# avr-fusebit-doctor-adapter-tqfp32.net
KiCad netlist of a schematic drawn in EAGLE
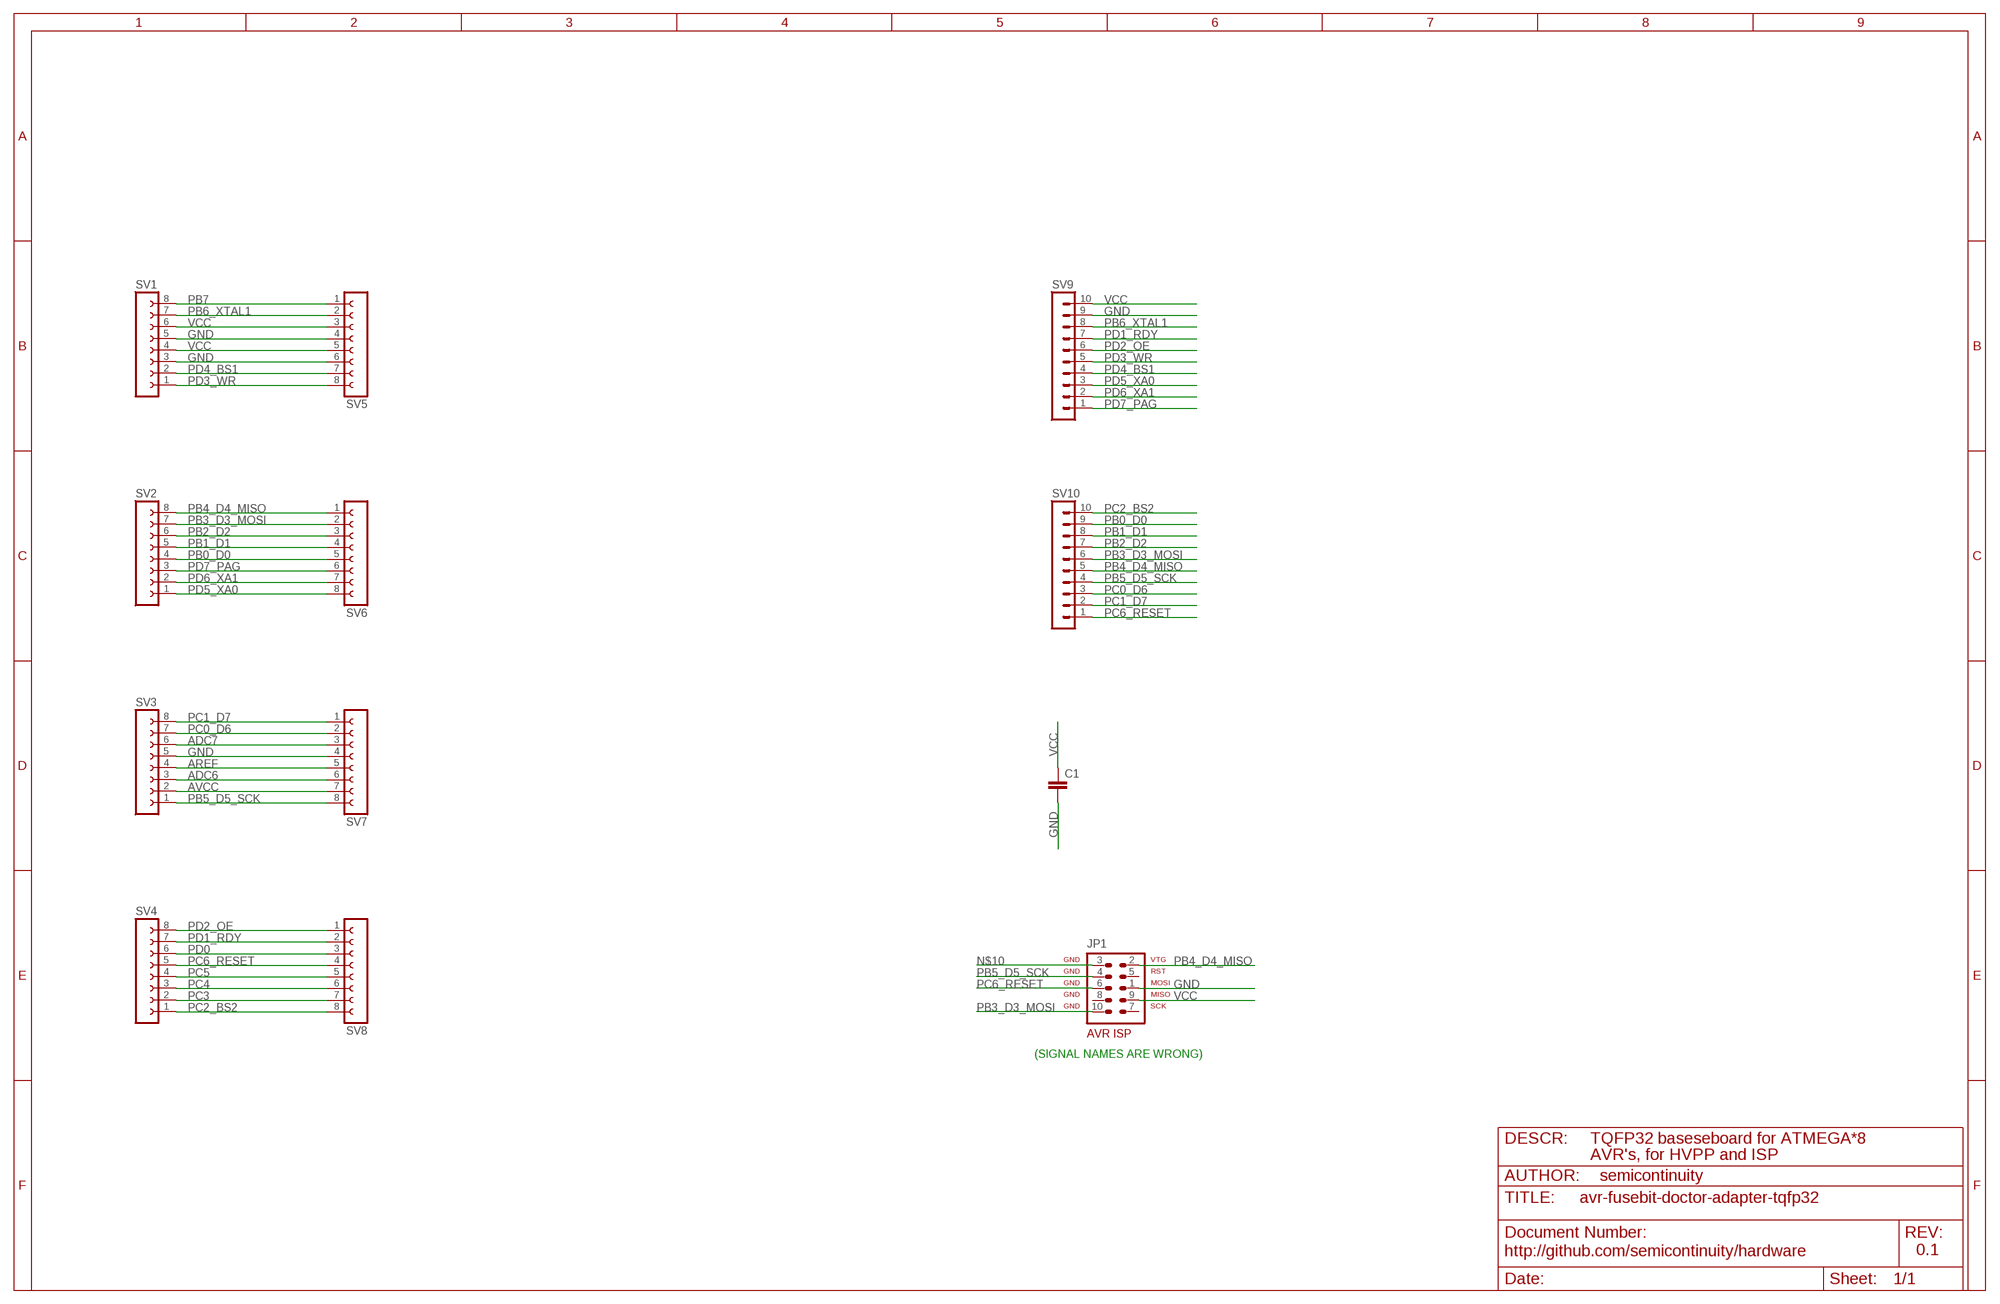
[diagram p0: schematic, sheet 1]

(export (version "E")
  (design (tool "Eeschema 10.0.6"))
  (components
    (comp (ref "C1")
      (value "C-EUC0805")
      (footprint "eagle-import:C0805")
      (libsource (lib "eagle-import") (part "C-EUC0805"))
    )
    (comp (ref "JP1")
      (value "AVR-ISP-10")
      (footprint "eagle-import:AVR-ISP-10")
      (libsource (lib "eagle-import") (part "AVR-ISP-10"))
    )
    (comp (ref "SV1")
      (value "FE08-1")
      (footprint "eagle-import:FE08")
      (libsource (lib "eagle-import") (part "FE08-1"))
    )
    (comp (ref "SV2")
      (value "FE08-1")
      (footprint "eagle-import:FE08")
      (libsource (lib "eagle-import") (part "FE08-1"))
    )
    (comp (ref "SV3")
      (value "FE08-1")
      (footprint "eagle-import:FE08")
      (libsource (lib "eagle-import") (part "FE08-1"))
    )
    (comp (ref "SV4")
      (value "FE08-1")
      (footprint "eagle-import:FE08")
      (libsource (lib "eagle-import") (part "FE08-1"))
    )
    (comp (ref "SV5")
      (value "FE08-1")
      (footprint "eagle-import:FE08")
      (libsource (lib "eagle-import") (part "FE08-1"))
    )
    (comp (ref "SV6")
      (value "FE08-1")
      (footprint "eagle-import:FE08")
      (libsource (lib "eagle-import") (part "FE08-1"))
    )
    (comp (ref "SV7")
      (value "FE08-1")
      (footprint "eagle-import:FE08")
      (libsource (lib "eagle-import") (part "FE08-1"))
    )
    (comp (ref "SV8")
      (value "FE08-1")
      (footprint "eagle-import:FE08")
      (libsource (lib "eagle-import") (part "FE08-1"))
    )
    (comp (ref "SV9")
      (value "MA10-1")
      (footprint "eagle-import:MA10-1")
      (libsource (lib "eagle-import") (part "MA10-1"))
    )
    (comp (ref "SV10")
      (value "MA10-1")
      (footprint "eagle-import:MA10-1")
      (libsource (lib "eagle-import") (part "MA10-1"))
    )
  )
  (nets
    (net (code "1") (name "/ADC6") (class "Default")
      (node (ref "SV3") (pin "3") (pinfunction "3_3") (pintype "passive"))
      (node (ref "SV7") (pin "6") (pinfunction "6_6") (pintype "passive"))
    )
    (net (code "2") (name "/ADC7") (class "Default")
      (node (ref "SV3") (pin "6") (pinfunction "6_6") (pintype "passive"))
      (node (ref "SV7") (pin "3") (pinfunction "3_3") (pintype "passive"))
    )
    (net (code "3") (name "/AREF") (class "Default")
      (node (ref "SV3") (pin "4") (pinfunction "4_4") (pintype "passive"))
      (node (ref "SV7") (pin "5") (pinfunction "5_5") (pintype "passive"))
    )
    (net (code "4") (name "/AVCC") (class "Default")
      (node (ref "SV3") (pin "2") (pinfunction "2_2") (pintype "passive"))
      (node (ref "SV7") (pin "7") (pinfunction "7_7") (pintype "passive"))
    )
    (net (code "5") (name "/GND") (class "Default")
      (node (ref "C1") (pin "2") (pinfunction "2_2") (pintype "passive"))
      (node (ref "JP1") (pin "1") (pinfunction "1_1") (pintype "passive"))
      (node (ref "SV1") (pin "3") (pinfunction "3_3") (pintype "passive"))
      (node (ref "SV1") (pin "5") (pinfunction "5_5") (pintype "passive"))
      (node (ref "SV3") (pin "5") (pinfunction "5_5") (pintype "passive"))
      (node (ref "SV5") (pin "4") (pinfunction "4_4") (pintype "passive"))
      (node (ref "SV5") (pin "6") (pinfunction "6_6") (pintype "passive"))
      (node (ref "SV7") (pin "4") (pinfunction "4_4") (pintype "passive"))
      (node (ref "SV9") (pin "9") (pinfunction "9_9") (pintype "passive"))
    )
    (net (code "6") (name "/N$10") (class "Default")
      (node (ref "JP1") (pin "3") (pinfunction "3_3") (pintype "passive"))
    )
    (net (code "7") (name "/PB0_D0") (class "Default")
      (node (ref "SV10") (pin "9") (pinfunction "9_9") (pintype "passive"))
      (node (ref "SV2") (pin "4") (pinfunction "4_4") (pintype "passive"))
      (node (ref "SV6") (pin "5") (pinfunction "5_5") (pintype "passive"))
    )
    (net (code "8") (name "/PB1_D1") (class "Default")
      (node (ref "SV10") (pin "8") (pinfunction "8_8") (pintype "passive"))
      (node (ref "SV2") (pin "5") (pinfunction "5_5") (pintype "passive"))
      (node (ref "SV6") (pin "4") (pinfunction "4_4") (pintype "passive"))
    )
    (net (code "9") (name "/PB2_D2") (class "Default")
      (node (ref "SV10") (pin "7") (pinfunction "7_7") (pintype "passive"))
      (node (ref "SV2") (pin "6") (pinfunction "6_6") (pintype "passive"))
      (node (ref "SV6") (pin "3") (pinfunction "3_3") (pintype "passive"))
    )
    (net (code "10") (name "/PB3_D3_MOSI") (class "Default")
      (node (ref "JP1") (pin "10") (pinfunction "10_10") (pintype "passive"))
      (node (ref "SV10") (pin "6") (pinfunction "6_6") (pintype "passive"))
      (node (ref "SV2") (pin "7") (pinfunction "7_7") (pintype "passive"))
      (node (ref "SV6") (pin "2") (pinfunction "2_2") (pintype "passive"))
    )
    (net (code "11") (name "/PB4_D4_MISO") (class "Default")
      (node (ref "JP1") (pin "2") (pinfunction "2_2") (pintype "passive"))
      (node (ref "SV10") (pin "5") (pinfunction "5_5") (pintype "passive"))
      (node (ref "SV2") (pin "8") (pinfunction "8_8") (pintype "passive"))
      (node (ref "SV6") (pin "1") (pinfunction "1_1") (pintype "passive"))
    )
    (net (code "12") (name "/PB5_D5_SCK") (class "Default")
      (node (ref "JP1") (pin "4") (pinfunction "4_4") (pintype "passive"))
      (node (ref "SV10") (pin "4") (pinfunction "4_4") (pintype "passive"))
      (node (ref "SV3") (pin "1") (pinfunction "1_1") (pintype "passive"))
      (node (ref "SV7") (pin "8") (pinfunction "8_8") (pintype "passive"))
    )
    (net (code "13") (name "/PB6_XTAL1") (class "Default")
      (node (ref "SV1") (pin "7") (pinfunction "7_7") (pintype "passive"))
      (node (ref "SV5") (pin "2") (pinfunction "2_2") (pintype "passive"))
      (node (ref "SV9") (pin "8") (pinfunction "8_8") (pintype "passive"))
    )
    (net (code "14") (name "/PB7") (class "Default")
      (node (ref "SV1") (pin "8") (pinfunction "8_8") (pintype "passive"))
      (node (ref "SV5") (pin "1") (pinfunction "1_1") (pintype "passive"))
    )
    (net (code "15") (name "/PC0_D6") (class "Default")
      (node (ref "SV10") (pin "3") (pinfunction "3_3") (pintype "passive"))
      (node (ref "SV3") (pin "7") (pinfunction "7_7") (pintype "passive"))
      (node (ref "SV7") (pin "2") (pinfunction "2_2") (pintype "passive"))
    )
    (net (code "16") (name "/PC1_D7") (class "Default")
      (node (ref "SV10") (pin "2") (pinfunction "2_2") (pintype "passive"))
      (node (ref "SV3") (pin "8") (pinfunction "8_8") (pintype "passive"))
      (node (ref "SV7") (pin "1") (pinfunction "1_1") (pintype "passive"))
    )
    (net (code "17") (name "/PC2_BS2") (class "Default")
      (node (ref "SV10") (pin "10") (pinfunction "10_10") (pintype "passive"))
      (node (ref "SV4") (pin "1") (pinfunction "1_1") (pintype "passive"))
      (node (ref "SV8") (pin "8") (pinfunction "8_8") (pintype "passive"))
    )
    (net (code "18") (name "/PC3") (class "Default")
      (node (ref "SV4") (pin "2") (pinfunction "2_2") (pintype "passive"))
      (node (ref "SV8") (pin "7") (pinfunction "7_7") (pintype "passive"))
    )
    (net (code "19") (name "/PC4") (class "Default")
      (node (ref "SV4") (pin "3") (pinfunction "3_3") (pintype "passive"))
      (node (ref "SV8") (pin "6") (pinfunction "6_6") (pintype "passive"))
    )
    (net (code "20") (name "/PC5") (class "Default")
      (node (ref "SV4") (pin "4") (pinfunction "4_4") (pintype "passive"))
      (node (ref "SV8") (pin "5") (pinfunction "5_5") (pintype "passive"))
    )
    (net (code "21") (name "/PC6_RESET") (class "Default")
      (node (ref "JP1") (pin "6") (pinfunction "6_6") (pintype "passive"))
      (node (ref "SV10") (pin "1") (pinfunction "1_1") (pintype "passive"))
      (node (ref "SV4") (pin "5") (pinfunction "5_5") (pintype "passive"))
      (node (ref "SV8") (pin "4") (pinfunction "4_4") (pintype "passive"))
    )
    (net (code "22") (name "/PD0") (class "Default")
      (node (ref "SV4") (pin "6") (pinfunction "6_6") (pintype "passive"))
      (node (ref "SV8") (pin "3") (pinfunction "3_3") (pintype "passive"))
    )
    (net (code "23") (name "/PD1_RDY") (class "Default")
      (node (ref "SV4") (pin "7") (pinfunction "7_7") (pintype "passive"))
      (node (ref "SV8") (pin "2") (pinfunction "2_2") (pintype "passive"))
      (node (ref "SV9") (pin "7") (pinfunction "7_7") (pintype "passive"))
    )
    (net (code "24") (name "/PD2_OE") (class "Default")
      (node (ref "SV4") (pin "8") (pinfunction "8_8") (pintype "passive"))
      (node (ref "SV8") (pin "1") (pinfunction "1_1") (pintype "passive"))
      (node (ref "SV9") (pin "6") (pinfunction "6_6") (pintype "passive"))
    )
    (net (code "25") (name "/PD3_WR") (class "Default")
      (node (ref "SV1") (pin "1") (pinfunction "1_1") (pintype "passive"))
      (node (ref "SV5") (pin "8") (pinfunction "8_8") (pintype "passive"))
      (node (ref "SV9") (pin "5") (pinfunction "5_5") (pintype "passive"))
    )
    (net (code "26") (name "/PD4_BS1") (class "Default")
      (node (ref "SV1") (pin "2") (pinfunction "2_2") (pintype "passive"))
      (node (ref "SV5") (pin "7") (pinfunction "7_7") (pintype "passive"))
      (node (ref "SV9") (pin "4") (pinfunction "4_4") (pintype "passive"))
    )
    (net (code "27") (name "/PD5_XA0") (class "Default")
      (node (ref "SV2") (pin "1") (pinfunction "1_1") (pintype "passive"))
      (node (ref "SV6") (pin "8") (pinfunction "8_8") (pintype "passive"))
      (node (ref "SV9") (pin "3") (pinfunction "3_3") (pintype "passive"))
    )
    (net (code "28") (name "/PD6_XA1") (class "Default")
      (node (ref "SV2") (pin "2") (pinfunction "2_2") (pintype "passive"))
      (node (ref "SV6") (pin "7") (pinfunction "7_7") (pintype "passive"))
      (node (ref "SV9") (pin "2") (pinfunction "2_2") (pintype "passive"))
    )
    (net (code "29") (name "/PD7_PAG") (class "Default")
      (node (ref "SV2") (pin "3") (pinfunction "3_3") (pintype "passive"))
      (node (ref "SV6") (pin "6") (pinfunction "6_6") (pintype "passive"))
      (node (ref "SV9") (pin "1") (pinfunction "1_1") (pintype "passive"))
    )
    (net (code "30") (name "/VCC") (class "Default")
      (node (ref "C1") (pin "1") (pinfunction "1_1") (pintype "passive"))
      (node (ref "JP1") (pin "9") (pinfunction "9_9") (pintype "passive"))
      (node (ref "SV1") (pin "4") (pinfunction "4_4") (pintype "passive"))
      (node (ref "SV1") (pin "6") (pinfunction "6_6") (pintype "passive"))
      (node (ref "SV5") (pin "3") (pinfunction "3_3") (pintype "passive"))
      (node (ref "SV5") (pin "5") (pinfunction "5_5") (pintype "passive"))
      (node (ref "SV9") (pin "10") (pinfunction "10_10") (pintype "passive"))
    )
    (net (code "31") (name "unconnected-(JP1-Pad5)") (class "Default")
      (node (ref "JP1") (pin "5") (pinfunction "5_5") (pintype "passive"))
    )
    (net (code "32") (name "unconnected-(JP1-Pad7)") (class "Default")
      (node (ref "JP1") (pin "7") (pinfunction "7_7") (pintype "passive"))
    )
    (net (code "33") (name "unconnected-(JP1-Pad8)") (class "Default")
      (node (ref "JP1") (pin "8") (pinfunction "8_8") (pintype "passive"))
    )
  )
)
